# SensorTCRT5000.net
KiCad netlist of a schematic drawn in EAGLE
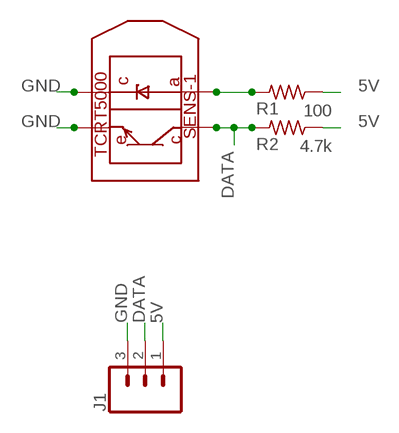
[diagram p0: schematic, sheet 1]

(export (version "E")
  (design (tool "Eeschema 10.0.6"))
  (components
    (comp (ref "J1")
      (value "CONN_03")
      (footprint "eagle-import:1X03")
      (libsource (lib "eagle-import") (part "CONN_03"))
    )
    (comp (ref "R1")
      (value "100")
      (footprint "eagle-import:0207_10")
      (libsource (lib "eagle-import") (part "R-US_0207/10"))
    )
    (comp (ref "R2")
      (value "4.7k")
      (footprint "eagle-import:0207_10")
      (libsource (lib "eagle-import") (part "R-US_0207/10"))
    )
    (comp (ref "SENS-1")
      (value "TCRT5000")
      (footprint "eagle-import:5000")
      (libsource (lib "eagle-import") (part "TCRT5000"))
    )
  )
  (nets
    (net (code "1") (name "/5V") (class "Default")
      (node (ref "J1") (pin "1") (pinfunction "1_1") (pintype "passive"))
      (node (ref "R1") (pin "1") (pinfunction "1_1") (pintype "passive"))
      (node (ref "R2") (pin "1") (pinfunction "1_1") (pintype "passive"))
    )
    (net (code "2") (name "/DATA") (class "Default")
      (node (ref "J1") (pin "2") (pinfunction "2_2") (pintype "passive"))
      (node (ref "R2") (pin "2") (pinfunction "2_2") (pintype "passive"))
      (node (ref "SENS-1") (pin "P$1") (pinfunction "P$1_P$1") (pintype "passive"))
    )
    (net (code "3") (name "/GND") (class "Default")
      (node (ref "J1") (pin "3") (pinfunction "3_3") (pintype "passive"))
      (node (ref "SENS-1") (pin "P$2") (pinfunction "P$2_P$2") (pintype "passive"))
      (node (ref "SENS-1") (pin "P$4") (pinfunction "P$4_P$4") (pintype "passive"))
    )
    (net (code "4") (name "Net-(R1-Pad2)") (class "Default")
      (node (ref "R1") (pin "2") (pinfunction "2_2") (pintype "passive"))
      (node (ref "SENS-1") (pin "P$3") (pinfunction "P$3_P$3") (pintype "passive"))
    )
  )
)
